# kfly_v3_0.net
KiCad netlist of a schematic drawn in EAGLE
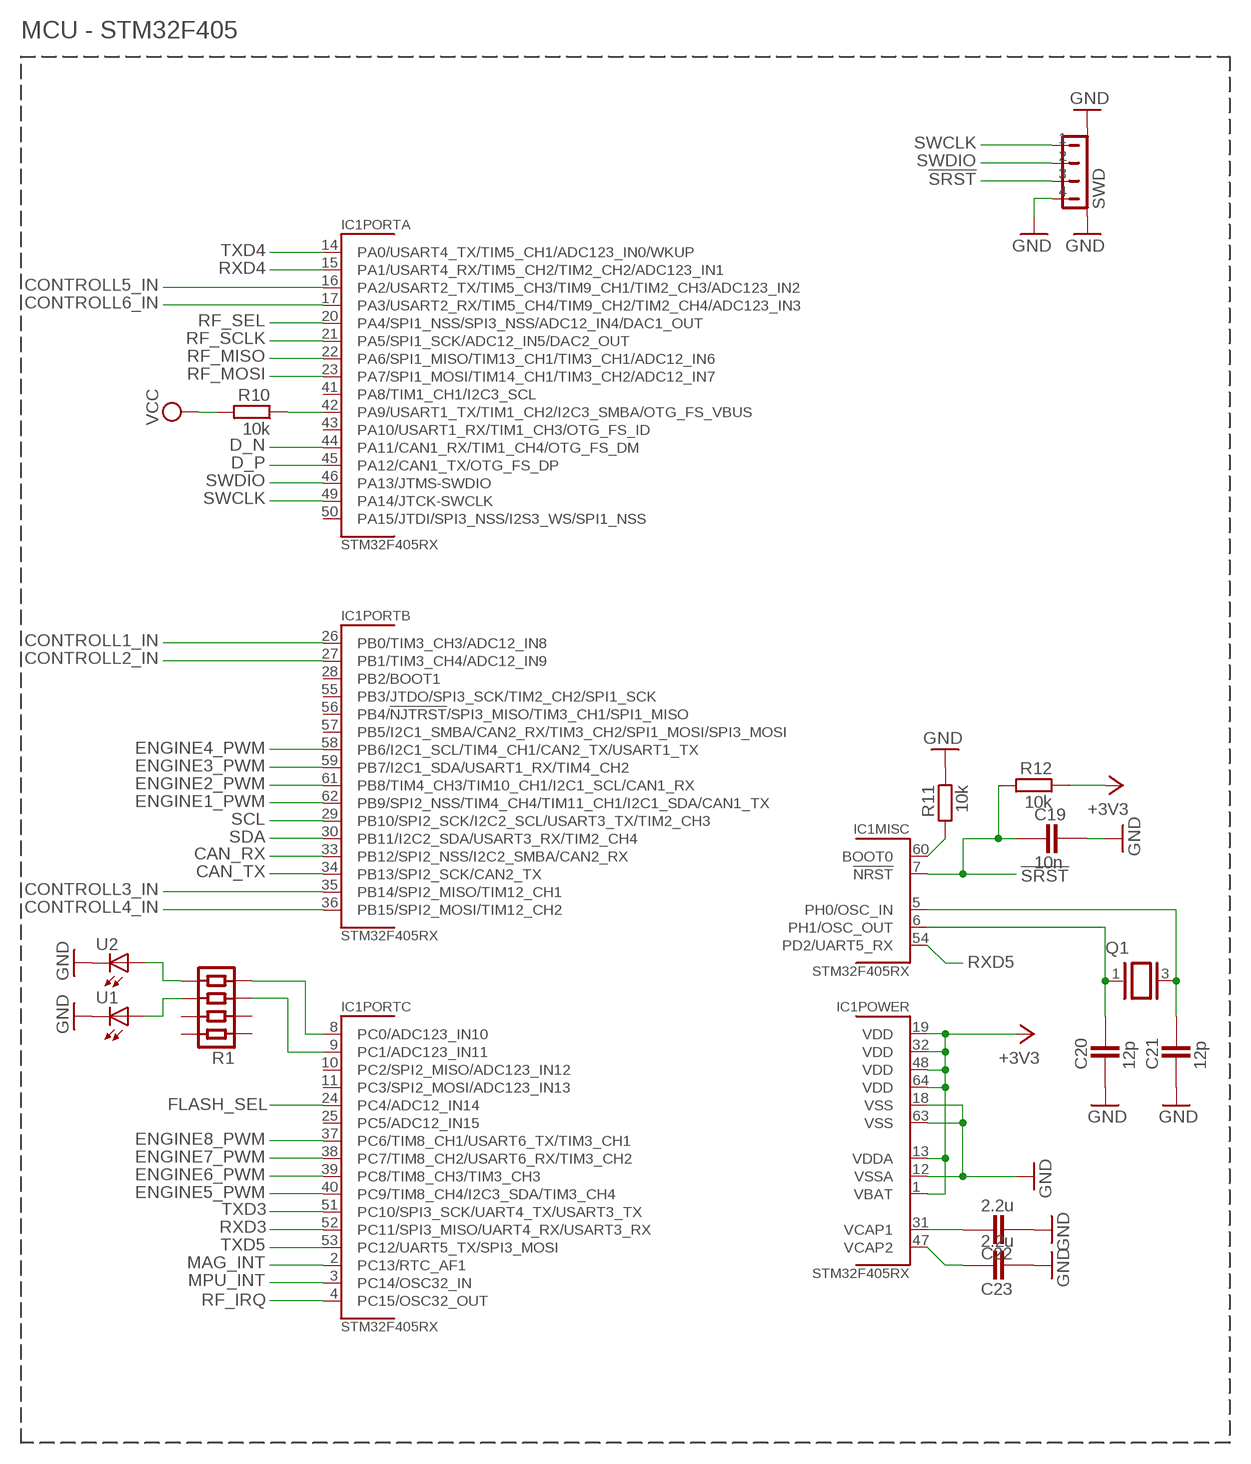
[diagram p0: schematic, sheet 1]
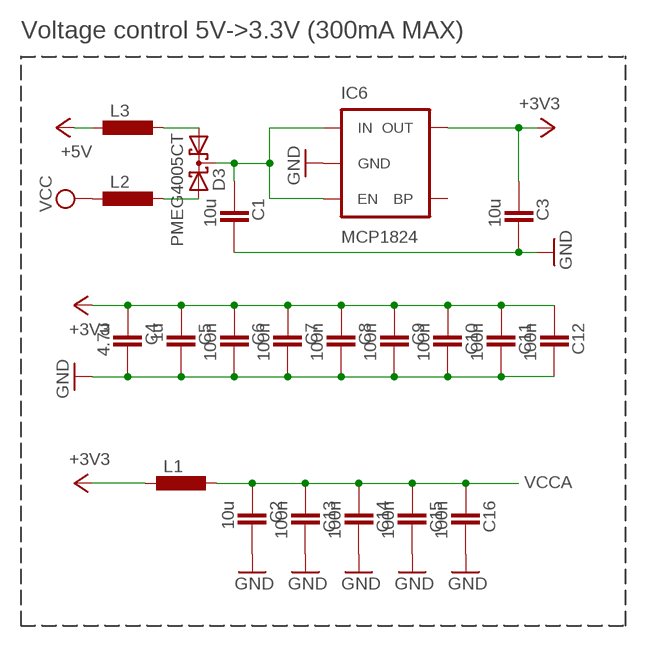
[diagram p1: schematic, sheet 2]
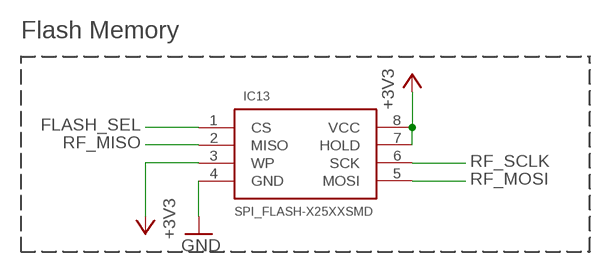
[diagram p2: schematic, sheet 3]
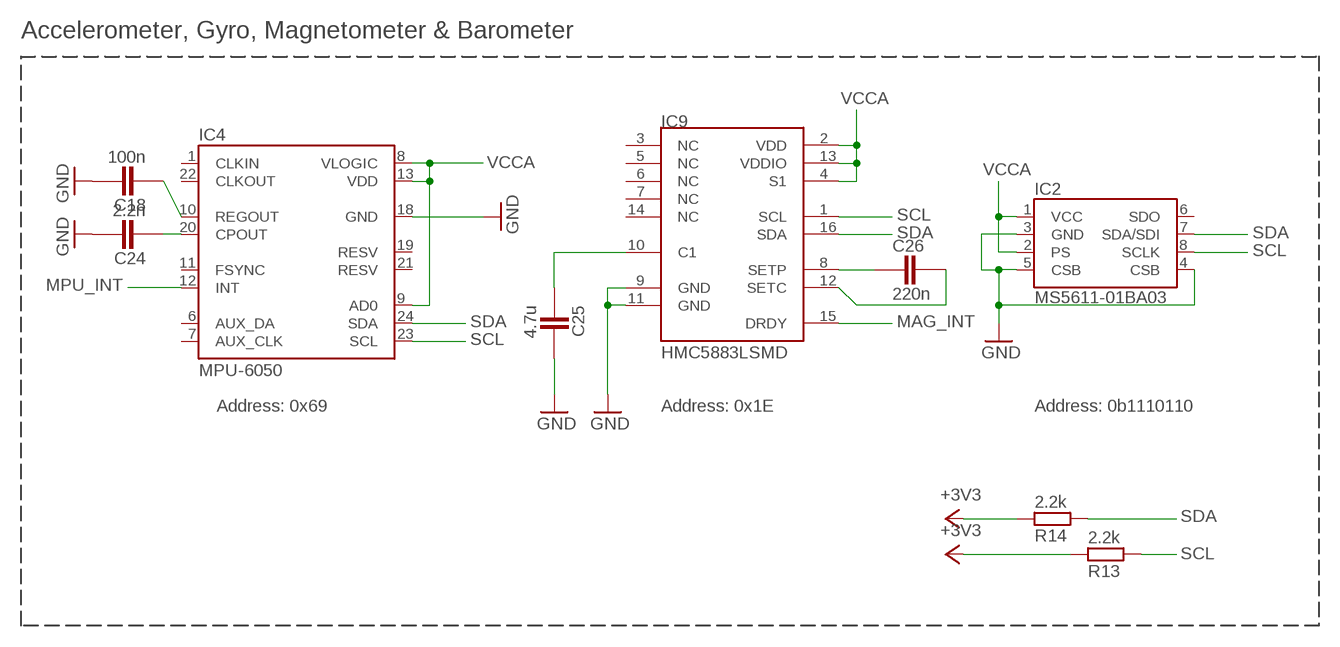
[diagram p3: schematic, sheet 4]
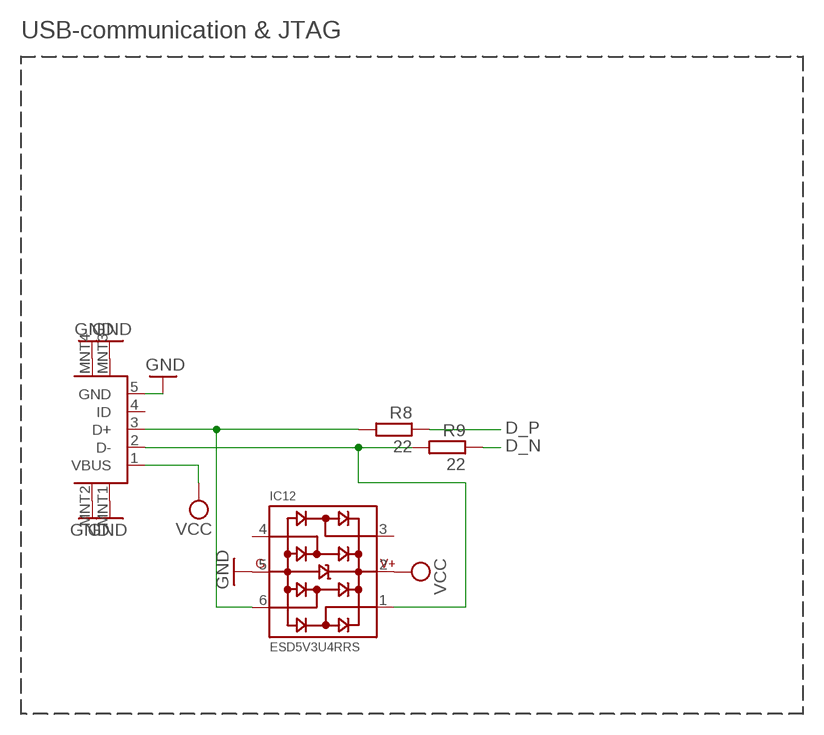
[diagram p4: schematic, sheet 5]
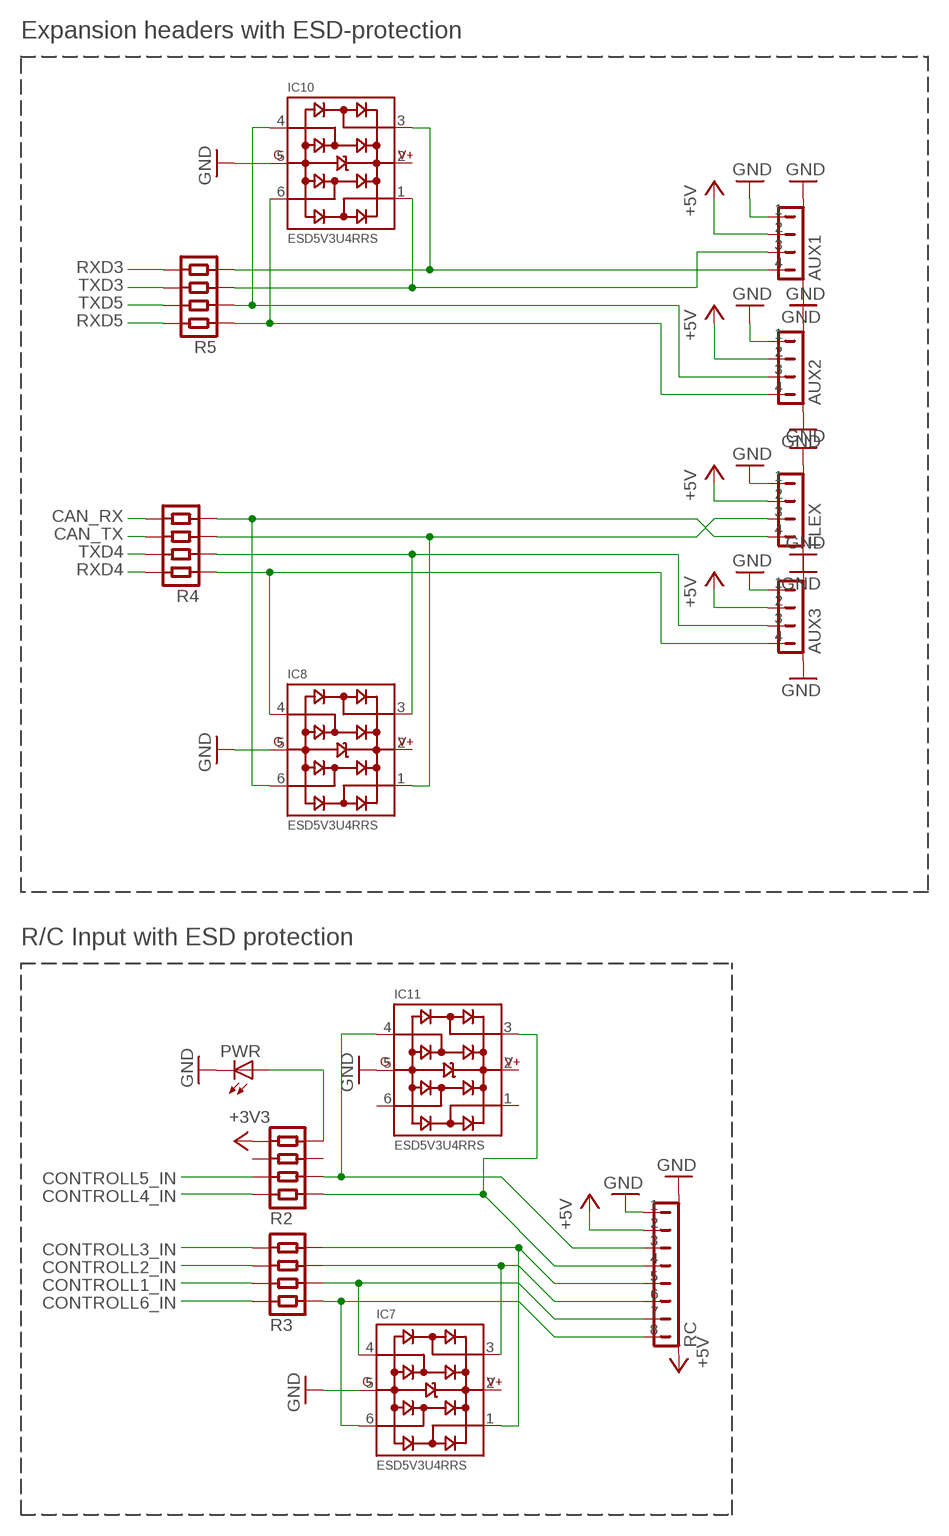
[diagram p5: schematic, sheet 6]
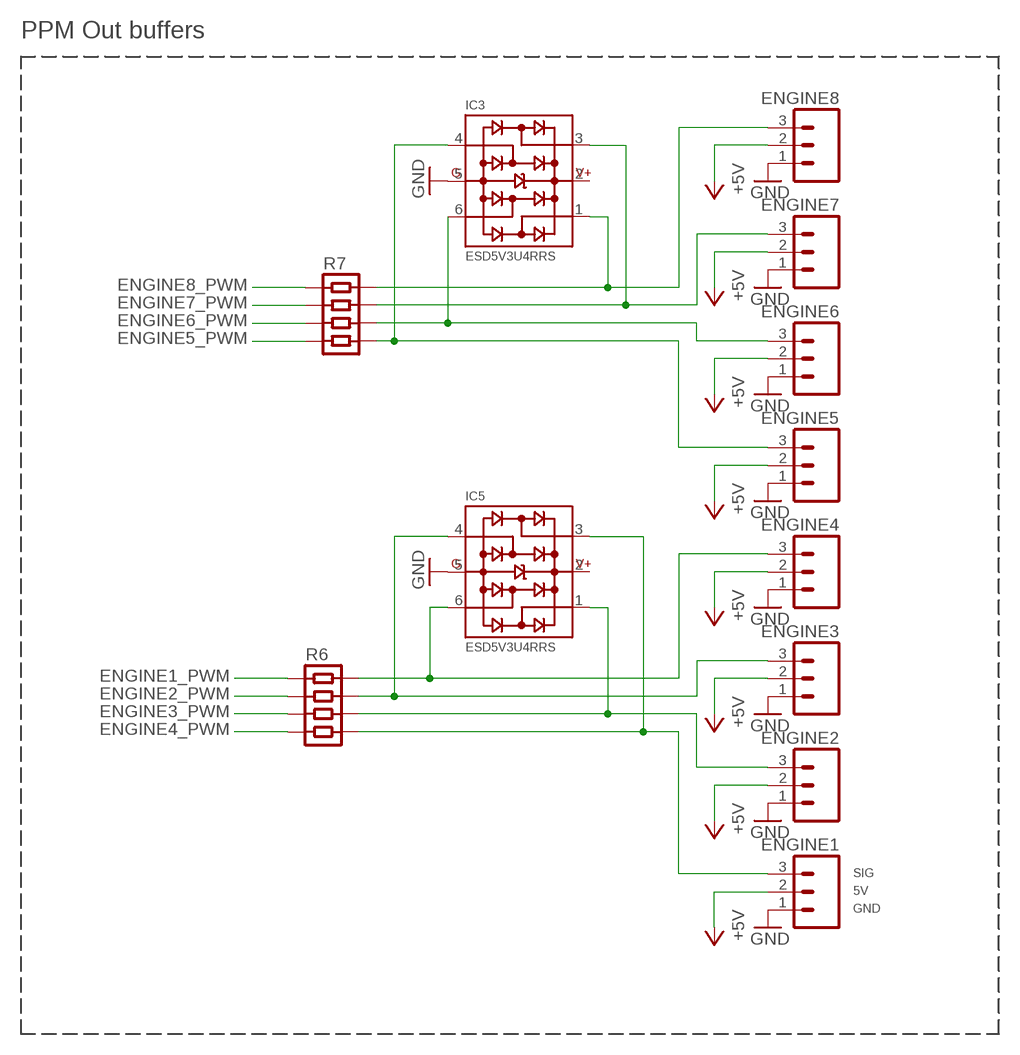
[diagram p6: schematic, sheet 7]
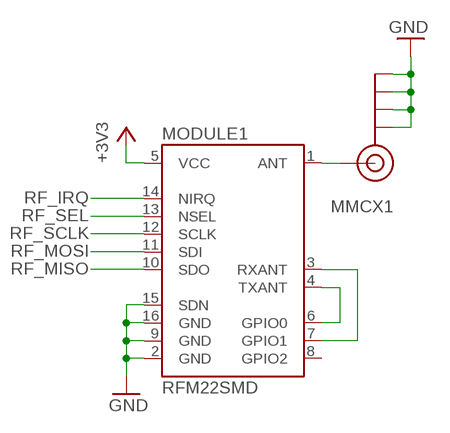
[diagram p7: schematic, sheet 8]

(export (version "E")
  (design (tool "Eeschema 10.0.6"))
  (components
    (comp (ref "C18")
      (value "100n")
      (footprint "eagle-import:CAPC1005X60N")
      (libsource (lib "eagle-import") (part "CAPACITOR_0402"))
    )
    (comp (ref "C24")
      (value "2.2n")
      (footprint "eagle-import:CAPC1005X60N")
      (libsource (lib "eagle-import") (part "CAPACITOR_0402"))
    )
    (comp (ref "C25")
      (value "4.7u")
      (footprint "eagle-import:CAPC1608X92N")
      (libsource (lib "eagle-import") (part "CAPACITOR_0603"))
    )
    (comp (ref "C26")
      (value "220n")
      (footprint "eagle-import:CAPC1608X92N")
      (libsource (lib "eagle-import") (part "CAPACITOR_0603"))
    )
    (comp (ref "IC2")
      (value "MS5611-01BA03")
      (footprint "eagle-import:MS5611")
      (libsource (lib "eagle-import") (part "MS5611-01BA01"))
    )
    (comp (ref "IC4")
      (value "MPU-6050")
      (footprint "eagle-import:QFN-24")
      (libsource (lib "eagle-import") (part "MPU-6050"))
    )
    (comp (ref "IC9")
      (value "HMC5883LSMD")
      (footprint "eagle-import:16LPCC")
      (libsource (lib "eagle-import") (part "HMC5883LSMD"))
    )
    (comp (ref "R13")
      (value "2.2k")
      (footprint "eagle-import:RESC1005X40AN")
      (libsource (lib "eagle-import") (part "RESISTOR_0402"))
    )
    (comp (ref "R14")
      (value "2.2k")
      (footprint "eagle-import:RESC1005X40AN")
      (libsource (lib "eagle-import") (part "RESISTOR_0402"))
    )
    (comp (ref "AUX1")
      (value "JST-4PIN-SIDE-1.0")
      (footprint "eagle-import:JST-4PIN-SIDE")
      (libsource (lib "eagle-import") (part "JST-4PIN-SIDE-1.0"))
    )
    (comp (ref "AUX2")
      (value "JST-4PIN-SIDE-1.0")
      (footprint "eagle-import:JST-4PIN-SIDE")
      (libsource (lib "eagle-import") (part "JST-4PIN-SIDE-1.0"))
    )
    (comp (ref "AUX3")
      (value "JST-4PIN-SIDE-1.0")
      (footprint "eagle-import:JST-4PIN-SIDE")
      (libsource (lib "eagle-import") (part "JST-4PIN-SIDE-1.0"))
    )
    (comp (ref "FLEX")
      (value "JST-4PIN-SIDE-1.0")
      (footprint "eagle-import:JST-4PIN-SIDE")
      (libsource (lib "eagle-import") (part "JST-4PIN-SIDE-1.0"))
    )
    (comp (ref "IC7")
      (value "ESD5V3U4RRS")
      (footprint "eagle-import:SOT363")
      (libsource (lib "eagle-import") (part "ESD5V3U4RRS"))
    )
    (comp (ref "IC8")
      (value "ESD5V3U4RRS")
      (footprint "eagle-import:SOT363")
      (libsource (lib "eagle-import") (part "ESD5V3U4RRS"))
    )
    (comp (ref "IC10")
      (value "ESD5V3U4RRS")
      (footprint "eagle-import:SOT363")
      (libsource (lib "eagle-import") (part "ESD5V3U4RRS"))
    )
    (comp (ref "IC11")
      (value "ESD5V3U4RRS")
      (footprint "eagle-import:SOT363")
      (libsource (lib "eagle-import") (part "ESD5V3U4RRS"))
    )
    (comp (ref "PWR")
      (value "LED0603")
      (footprint "eagle-import:LED-0603")
      (libsource (lib "eagle-import") (part "LED0603"))
    )
    (comp (ref "R2")
      (value "RESISTOR-4ARRAY-0804")
      (footprint "eagle-import:RESISTORARRAY_0804")
      (libsource (lib "eagle-import") (part "RESISTOR-4ARRAY-0804"))
    )
    (comp (ref "R3")
      (value "RESISTOR-4ARRAY-0804")
      (footprint "eagle-import:RESISTORARRAY_0804")
      (libsource (lib "eagle-import") (part "RESISTOR-4ARRAY-0804"))
    )
    (comp (ref "R4")
      (value "RESISTOR-4ARRAY-0804")
      (footprint "eagle-import:RESISTORARRAY_0804")
      (libsource (lib "eagle-import") (part "RESISTOR-4ARRAY-0804"))
    )
    (comp (ref "R5")
      (value "RESISTOR-4ARRAY-0804")
      (footprint "eagle-import:RESISTORARRAY_0804")
      (libsource (lib "eagle-import") (part "RESISTOR-4ARRAY-0804"))
    )
    (comp (ref "RC")
      (value "JST-8PIN-SIDE-1.0")
      (footprint "eagle-import:JST-8PIN-SIDE")
      (libsource (lib "eagle-import") (part "JST-8PIN-SIDE-1.0"))
    )
    (comp (ref "C19")
      (value "10n")
      (footprint "eagle-import:CAPC1005X60N")
      (libsource (lib "eagle-import") (part "CAPACITOR_0402"))
    )
    (comp (ref "C20")
      (value "12p")
      (footprint "eagle-import:CAPC1005X60N")
      (libsource (lib "eagle-import") (part "CAPACITOR_0402"))
    )
    (comp (ref "C21")
      (value "12p")
      (footprint "eagle-import:CAPC1005X60N")
      (libsource (lib "eagle-import") (part "CAPACITOR_0402"))
    )
    (comp (ref "C22")
      (value "2.2u")
      (footprint "eagle-import:CAPC1608X92N")
      (libsource (lib "eagle-import") (part "CAPACITOR_0603"))
    )
    (comp (ref "C23")
      (value "2.2u")
      (footprint "eagle-import:CAPC1608X92N")
      (libsource (lib "eagle-import") (part "CAPACITOR_0603"))
    )
    (comp (ref "IC1")
      (value "STM32F405RX")
      (footprint "eagle-import:LQFP64-10X10")
      (libsource (lib "eagle-import") (part "STM32F4X5RX"))
    )
    (comp (ref "Q1")
      (value "2.5X3.2CRYSTAL")
      (footprint "eagle-import:2.5X3.2CRYSTAL")
      (libsource (lib "eagle-import") (part "2.5X3.2CRYSTAL"))
    )
    (comp (ref "R1")
      (value "RESISTOR-4ARRAY-0804")
      (footprint "eagle-import:RESISTORARRAY_0804")
      (libsource (lib "eagle-import") (part "RESISTOR-4ARRAY-0804"))
    )
    (comp (ref "R10")
      (value "10k")
      (footprint "eagle-import:RESC1005X40AN")
      (libsource (lib "eagle-import") (part "RESISTOR_0402"))
    )
    (comp (ref "R11")
      (value "10k")
      (footprint "eagle-import:RESC1005X40AN")
      (libsource (lib "eagle-import") (part "RESISTOR_0402"))
    )
    (comp (ref "R12")
      (value "10k")
      (footprint "eagle-import:RESC1005X40AN")
      (libsource (lib "eagle-import") (part "RESISTOR_0402"))
    )
    (comp (ref "SWD")
      (value "JST-4PIN-SIDE-1.0")
      (footprint "eagle-import:JST-4PIN-SIDE")
      (libsource (lib "eagle-import") (part "JST-4PIN-SIDE-1.0"))
    )
    (comp (ref "U1")
      (value "LED0603")
      (footprint "eagle-import:LED-0603")
      (libsource (lib "eagle-import") (part "LED0603"))
    )
    (comp (ref "U2")
      (value "LED0603")
      (footprint "eagle-import:LED-0603")
      (libsource (lib "eagle-import") (part "LED0603"))
    )
    (comp (ref "IC13")
      (value "SPI_FLASH-X25XXSMD")
      (footprint "eagle-import:SO08")
      (libsource (lib "eagle-import") (part "SPI_FLASH-X25XXSMD"))
    )
    (comp (ref "C1")
      (value "10u")
      (footprint "eagle-import:CAPC1608X92N")
      (libsource (lib "eagle-import") (part "CAPACITOR_0603"))
    )
    (comp (ref "C2")
      (value "10u")
      (footprint "eagle-import:CAPC1608X92N")
      (libsource (lib "eagle-import") (part "CAPACITOR_0603"))
    )
    (comp (ref "C3")
      (value "10u")
      (footprint "eagle-import:CAPC1608X92N")
      (libsource (lib "eagle-import") (part "CAPACITOR_0603"))
    )
    (comp (ref "C4")
      (value "4.7u")
      (footprint "eagle-import:CAPC1608X92N")
      (libsource (lib "eagle-import") (part "CAPACITOR_0603"))
    )
    (comp (ref "C5")
      (value "1u")
      (footprint "eagle-import:CAPC1608X92N")
      (libsource (lib "eagle-import") (part "CAPACITOR_0603"))
    )
    (comp (ref "C6")
      (value "100n")
      (footprint "eagle-import:CAPC1005X60N")
      (libsource (lib "eagle-import") (part "CAPACITOR_0402"))
    )
    (comp (ref "C7")
      (value "100n")
      (footprint "eagle-import:CAPC1005X60N")
      (libsource (lib "eagle-import") (part "CAPACITOR_0402"))
    )
    (comp (ref "C8")
      (value "100n")
      (footprint "eagle-import:CAPC1005X60N")
      (libsource (lib "eagle-import") (part "CAPACITOR_0402"))
    )
    (comp (ref "C9")
      (value "100n")
      (footprint "eagle-import:CAPC1005X60N")
      (libsource (lib "eagle-import") (part "CAPACITOR_0402"))
    )
    (comp (ref "C10")
      (value "100n")
      (footprint "eagle-import:CAPC1005X60N")
      (libsource (lib "eagle-import") (part "CAPACITOR_0402"))
    )
    (comp (ref "C11")
      (value "100n")
      (footprint "eagle-import:CAPC1005X60N")
      (libsource (lib "eagle-import") (part "CAPACITOR_0402"))
    )
    (comp (ref "C12")
      (value "100n")
      (footprint "eagle-import:CAPC1005X60N")
      (libsource (lib "eagle-import") (part "CAPACITOR_0402"))
    )
    (comp (ref "C13")
      (value "100n")
      (footprint "eagle-import:CAPC1005X60N")
      (libsource (lib "eagle-import") (part "CAPACITOR_0402"))
    )
    (comp (ref "C14")
      (value "100n")
      (footprint "eagle-import:CAPC1005X60N")
      (libsource (lib "eagle-import") (part "CAPACITOR_0402"))
    )
    (comp (ref "C15")
      (value "100n")
      (footprint "eagle-import:CAPC1005X60N")
      (libsource (lib "eagle-import") (part "CAPACITOR_0402"))
    )
    (comp (ref "C16")
      (value "100n")
      (footprint "eagle-import:CAPC1005X60N")
      (libsource (lib "eagle-import") (part "CAPACITOR_0402"))
    )
    (comp (ref "D3")
      (value "PMEG4005CT")
      (footprint "eagle-import:SOT23")
      (libsource (lib "eagle-import") (part "BAS40-05"))
    )
    (comp (ref "IC6")
      (value "MCP1824")
      (footprint "eagle-import:SOT23-5")
      (libsource (lib "eagle-import") (part "V_REG_LDOSMD"))
    )
    (comp (ref "L1")
      (value "INDUCTOR_0603")
      (footprint "eagle-import:INDC1608X95N")
      (libsource (lib "eagle-import") (part "INDUCTOR_0603"))
    )
    (comp (ref "L2")
      (value "INDUCTOR_0603")
      (footprint "eagle-import:INDC1608X95N")
      (libsource (lib "eagle-import") (part "INDUCTOR_0603"))
    )
    (comp (ref "L3")
      (value "INDUCTOR_0603")
      (footprint "eagle-import:INDC1608X95N")
      (libsource (lib "eagle-import") (part "INDUCTOR_0603"))
    )
    (comp (ref "MMCX1")
      (value "MMCX")
      (footprint "eagle-import:MMCX_THROUGHHOLE_RIGHTANGLE")
      (libsource (lib "eagle-import") (part "MMCX"))
    )
    (comp (ref "MODULE1")
      (value "RFM22SMD")
      (footprint "eagle-import:RFM22-XXX-S2")
      (libsource (lib "eagle-import") (part "RFM22SMD"))
    )
    (comp (ref "IC12")
      (value "ESD5V3U4RRS")
      (footprint "eagle-import:SOT363")
      (libsource (lib "eagle-import") (part "ESD5V3U4RRS"))
    )
    (comp (ref "R8")
      (value "22")
      (footprint "eagle-import:RESC1005X40AN")
      (libsource (lib "eagle-import") (part "RESISTOR_0402"))
    )
    (comp (ref "R9")
      (value "22")
      (footprint "eagle-import:RESC1005X40AN")
      (libsource (lib "eagle-import") (part "RESISTOR_0402"))
    )
    (comp (ref "USB1")
      (value "USB-MICRO-B-BOTTOM")
      (footprint "eagle-import:MICROUSB_TYPEB_SURFACE")
      (libsource (lib "eagle-import") (part "USB-MICRO-B-BOTTOM"))
    )
    (comp (ref "ENGINE1")
      (value "M03")
      (footprint "eagle-import:M03")
      (libsource (lib "eagle-import") (part "M03"))
    )
    (comp (ref "ENGINE2")
      (value "M03")
      (footprint "eagle-import:M03")
      (libsource (lib "eagle-import") (part "M03"))
    )
    (comp (ref "ENGINE3")
      (value "M03")
      (footprint "eagle-import:M03")
      (libsource (lib "eagle-import") (part "M03"))
    )
    (comp (ref "ENGINE4")
      (value "M03")
      (footprint "eagle-import:M03")
      (libsource (lib "eagle-import") (part "M03"))
    )
    (comp (ref "ENGINE5")
      (value "M03")
      (footprint "eagle-import:M03")
      (libsource (lib "eagle-import") (part "M03"))
    )
    (comp (ref "ENGINE6")
      (value "M03")
      (footprint "eagle-import:M03")
      (libsource (lib "eagle-import") (part "M03"))
    )
    (comp (ref "ENGINE7")
      (value "M03")
      (footprint "eagle-import:M03")
      (libsource (lib "eagle-import") (part "M03"))
    )
    (comp (ref "ENGINE8")
      (value "M03")
      (footprint "eagle-import:M03")
      (libsource (lib "eagle-import") (part "M03"))
    )
    (comp (ref "IC3")
      (value "ESD5V3U4RRS")
      (footprint "eagle-import:SOT363")
      (libsource (lib "eagle-import") (part "ESD5V3U4RRS"))
    )
    (comp (ref "IC5")
      (value "ESD5V3U4RRS")
      (footprint "eagle-import:SOT363")
      (libsource (lib "eagle-import") (part "ESD5V3U4RRS"))
    )
    (comp (ref "R6")
      (value "RESISTOR-4ARRAY-0804")
      (footprint "eagle-import:RESISTORARRAY_0804")
      (libsource (lib "eagle-import") (part "RESISTOR-4ARRAY-0804"))
    )
    (comp (ref "R7")
      (value "RESISTOR-4ARRAY-0804")
      (footprint "eagle-import:RESISTORARRAY_0804")
      (libsource (lib "eagle-import") (part "RESISTOR-4ARRAY-0804"))
    )
  )
  (nets
    (net (code "1") (name "+3V3") (class "Default")
      (node (ref "C10") (pin "1") (pinfunction "1_1") (pintype "passive"))
      (node (ref "C11") (pin "1") (pinfunction "1_1") (pintype "passive"))
      (node (ref "C12") (pin "1") (pinfunction "1_1") (pintype "passive"))
      (node (ref "C3") (pin "1") (pinfunction "1_1") (pintype "passive"))
      (node (ref "C4") (pin "1") (pinfunction "1_1") (pintype "passive"))
      (node (ref "C5") (pin "1") (pinfunction "1_1") (pintype "passive"))
      (node (ref "C6") (pin "1") (pinfunction "1_1") (pintype "passive"))
      (node (ref "C7") (pin "1") (pinfunction "1_1") (pintype "passive"))
      (node (ref "C8") (pin "1") (pinfunction "1_1") (pintype "passive"))
      (node (ref "C9") (pin "1") (pinfunction "1_1") (pintype "passive"))
      (node (ref "IC1") (pin "1") (pinfunction "VBAT_1") (pintype "bidirectional"))
      (node (ref "IC1") (pin "13") (pinfunction "VDDA_13") (pintype "bidirectional"))
      (node (ref "IC1") (pin "19") (pinfunction "VDD_19") (pintype "bidirectional"))
      (node (ref "IC1") (pin "32") (pinfunction "VDD_32") (pintype "bidirectional"))
      (node (ref "IC1") (pin "48") (pinfunction "VDD_48") (pintype "bidirectional"))
      (node (ref "IC1") (pin "64") (pinfunction "VDD_64") (pintype "bidirectional"))
      (node (ref "IC13") (pin "3") (pinfunction "WP_3") (pintype "bidirectional"))
      (node (ref "IC13") (pin "7") (pinfunction "HOLD_7") (pintype "bidirectional"))
      (node (ref "IC13") (pin "8") (pinfunction "VCC_8") (pintype "bidirectional"))
      (node (ref "IC6") (pin "5") (pinfunction "OUT_5") (pintype "passive"))
      (node (ref "L1") (pin "1") (pinfunction "1_1") (pintype "passive"))
      (node (ref "MODULE1") (pin "5") (pinfunction "VCC_5") (pintype "bidirectional"))
      (node (ref "R12") (pin "1") (pinfunction "1_1") (pintype "passive"))
      (node (ref "R13") (pin "1") (pinfunction "1_1") (pintype "passive"))
      (node (ref "R14") (pin "1") (pinfunction "1_1") (pintype "passive"))
      (node (ref "R2") (pin "4") (pinfunction "4_4") (pintype "bidirectional"))
    )
    (net (code "2") (name "+5V") (class "Default")
      (node (ref "AUX1") (pin "2") (pinfunction "2_2") (pintype "bidirectional"))
      (node (ref "AUX2") (pin "2") (pinfunction "2_2") (pintype "bidirectional"))
      (node (ref "AUX3") (pin "2") (pinfunction "2_2") (pintype "bidirectional"))
      (node (ref "ENGINE1") (pin "2") (pinfunction "2_2") (pintype "passive"))
      (node (ref "ENGINE2") (pin "2") (pinfunction "2_2") (pintype "passive"))
      (node (ref "ENGINE3") (pin "2") (pinfunction "2_2") (pintype "passive"))
      (node (ref "ENGINE4") (pin "2") (pinfunction "2_2") (pintype "passive"))
      (node (ref "ENGINE5") (pin "2") (pinfunction "2_2") (pintype "passive"))
      (node (ref "ENGINE6") (pin "2") (pinfunction "2_2") (pintype "passive"))
      (node (ref "ENGINE7") (pin "2") (pinfunction "2_2") (pintype "passive"))
      (node (ref "ENGINE8") (pin "2") (pinfunction "2_2") (pintype "passive"))
      (node (ref "FLEX") (pin "2") (pinfunction "2_2") (pintype "bidirectional"))
      (node (ref "L3") (pin "1") (pinfunction "1_1") (pintype "passive"))
      (node (ref "RC") (pin "2") (pinfunction "2_2") (pintype "bidirectional"))
      (node (ref "RC") (pin "NC2") (pinfunction "GND2_NC2") (pintype "bidirectional"))
    )
    (net (code "3") (name "CAN_RX") (class "Default")
      (node (ref "IC1") (pin "33") (pinfunction "PB12/SPI2_NSS/I2C2_SMBA/CAN2_RX_33") (pintype "bidirectional"))
      (node (ref "R4") (pin "5") (pinfunction "5_5") (pintype "bidirectional"))
    )
    (net (code "4") (name "CAN_TX") (class "Default")
      (node (ref "IC1") (pin "34") (pinfunction "PB13/SPI2_SCK/CAN2_TX_34") (pintype "bidirectional"))
      (node (ref "R4") (pin "6") (pinfunction "6_6") (pintype "bidirectional"))
    )
    (net (code "5") (name "CONTROLL1_IN") (class "Default")
      (node (ref "IC1") (pin "26") (pinfunction "PB0/TIM3_CH3/ADC12_IN8_26") (pintype "bidirectional"))
      (node (ref "R3") (pin "2") (pinfunction "2_2") (pintype "bidirectional"))
    )
    (net (code "6") (name "CONTROLL2_IN") (class "Default")
      (node (ref "IC1") (pin "27") (pinfunction "PB1/TIM3_CH4/ADC12_IN9_27") (pintype "bidirectional"))
      (node (ref "R3") (pin "3") (pinfunction "3_3") (pintype "bidirectional"))
    )
    (net (code "7") (name "CONTROLL3_IN") (class "Default")
      (node (ref "IC1") (pin "35") (pinfunction "PB14/SPI2_MISO/TIM12_CH1_35") (pintype "bidirectional"))
      (node (ref "R3") (pin "4") (pinfunction "4_4") (pintype "bidirectional"))
    )
    (net (code "8") (name "CONTROLL4_IN") (class "Default")
      (node (ref "IC1") (pin "36") (pinfunction "PB15/SPI2_MOSI/TIM12_CH2_36") (pintype "bidirectional"))
      (node (ref "R2") (pin "1") (pinfunction "1_1") (pintype "bidirectional"))
    )
    (net (code "9") (name "CONTROLL5_IN") (class "Default")
      (node (ref "IC1") (pin "16") (pinfunction "PA2/USART2_TX/TIM5_CH3/TIM9_CH1/TIM2_CH3/ADC123_IN2_16") (pintype "bidirectional"))
      (node (ref "R2") (pin "2") (pinfunction "2_2") (pintype "bidirectional"))
    )
    (net (code "10") (name "CONTROLL6_IN") (class "Default")
      (node (ref "IC1") (pin "17") (pinfunction "PA3/USART2_RX/TIM5_CH4/TIM9_CH2/TIM2_CH4/ADC123_IN3_17") (pintype "bidirectional"))
      (node (ref "R3") (pin "1") (pinfunction "1_1") (pintype "bidirectional"))
    )
    (net (code "11") (name "D_N") (class "Default")
      (node (ref "IC1") (pin "44") (pinfunction "PA11/CAN1_RX/TIM1_CH4/OTG_FS_DM_44") (pintype "bidirectional"))
      (node (ref "R9") (pin "1") (pinfunction "1_1") (pintype "passive"))
    )
    (net (code "12") (name "D_P") (class "Default")
      (node (ref "IC1") (pin "45") (pinfunction "PA12/CAN1_TX/OTG_FS_DP_45") (pintype "bidirectional"))
      (node (ref "R8") (pin "1") (pinfunction "1_1") (pintype "passive"))
    )
    (net (code "13") (name "ENGINE1_PWM") (class "Default")
      (node (ref "IC1") (pin "62") (pinfunction "PB9/SPI2_NSS/TIM4_CH4/TIM11_CH1/I2C1_SDA/CAN1_TX_62") (pintype "bidirectional"))
      (node (ref "R6") (pin "1") (pinfunction "1_1") (pintype "bidirectional"))
    )
    (net (code "14") (name "ENGINE2_PWM") (class "Default")
      (node (ref "IC1") (pin "61") (pinfunction "PB8/TIM4_CH3/TIM10_CH1/I2C1_SCL/CAN1_RX_61") (pintype "bidirectional"))
      (node (ref "R6") (pin "2") (pinfunction "2_2") (pintype "bidirectional"))
    )
    (net (code "15") (name "ENGINE3_PWM") (class "Default")
      (node (ref "IC1") (pin "59") (pinfunction "PB7/I2C1_SDA/USART1_RX/TIM4_CH2_59") (pintype "bidirectional"))
      (node (ref "R6") (pin "3") (pinfunction "3_3") (pintype "bidirectional"))
    )
    (net (code "16") (name "ENGINE4_PWM") (class "Default")
      (node (ref "IC1") (pin "58") (pinfunction "PB6/I2C1_SCL/TIM4_CH1/CAN2_TX/USART1_TX_58") (pintype "bidirectional"))
      (node (ref "R6") (pin "4") (pinfunction "4_4") (pintype "bidirectional"))
    )
    (net (code "17") (name "ENGINE5_PWM") (class "Default")
      (node (ref "IC1") (pin "40") (pinfunction "PC9/TIM8_CH4/I2C3_SDA/TIM3_CH4_40") (pintype "bidirectional"))
      (node (ref "R7") (pin "4") (pinfunction "4_4") (pintype "bidirectional"))
    )
    (net (code "18") (name "ENGINE6_PWM") (class "Default")
      (node (ref "IC1") (pin "39") (pinfunction "PC8/TIM8_CH3/TIM3_CH3_39") (pintype "bidirectional"))
      (node (ref "R7") (pin "3") (pinfunction "3_3") (pintype "bidirectional"))
    )
    (net (code "19") (name "ENGINE7_PWM") (class "Default")
      (node (ref "IC1") (pin "38") (pinfunction "PC7/TIM8_CH2/USART6_RX/TIM3_CH2_38") (pintype "bidirectional"))
      (node (ref "R7") (pin "2") (pinfunction "2_2") (pintype "bidirectional"))
    )
    (net (code "20") (name "ENGINE8_PWM") (class "Default")
      (node (ref "IC1") (pin "37") (pinfunction "PC6/TIM8_CH1/USART6_TX/TIM3_CH1_37") (pintype "bidirectional"))
      (node (ref "R7") (pin "1") (pinfunction "1_1") (pintype "bidirectional"))
    )
    (net (code "21") (name "FLASH_SEL") (class "Default")
      (node (ref "IC1") (pin "24") (pinfunction "PC4/ADC12_IN14_24") (pintype "bidirectional"))
      (node (ref "IC13") (pin "1") (pinfunction "CS_1") (pintype "bidirectional"))
    )
    (net (code "22") (name "GND") (class "Default")
      (node (ref "AUX1") (pin "1") (pinfunction "1_1") (pintype "bidirectional"))
      (node (ref "AUX1") (pin "NC1") (pinfunction "P1_NC1") (pintype "bidirectional"))
      (node (ref "AUX1") (pin "NC2") (pinfunction "P2_NC2") (pintype "bidirectional"))
      (node (ref "AUX2") (pin "1") (pinfunction "1_1") (pintype "bidirectional"))
      (node (ref "AUX2") (pin "NC1") (pinfunction "P1_NC1") (pintype "bidirectional"))
      (node (ref "AUX2") (pin "NC2") (pinfunction "P2_NC2") (pintype "bidirectional"))
      (node (ref "AUX3") (pin "1") (pinfunction "1_1") (pintype "bidirectional"))
      (node (ref "AUX3") (pin "NC1") (pinfunction "P1_NC1") (pintype "bidirectional"))
      (node (ref "AUX3") (pin "NC2") (pinfunction "P2_NC2") (pintype "bidirectional"))
      (node (ref "C1") (pin "2") (pinfunction "2_2") (pintype "passive"))
      (node (ref "C10") (pin "2") (pinfunction "2_2") (pintype "passive"))
      (node (ref "C11") (pin "2") (pinfunction "2_2") (pintype "passive"))
      (node (ref "C12") (pin "2") (pinfunction "2_2") (pintype "passive"))
      (node (ref "C13") (pin "2") (pinfunction "2_2") (pintype "passive"))
      (node (ref "C14") (pin "2") (pinfunction "2_2") (pintype "passive"))
      (node (ref "C15") (pin "2") (pinfunction "2_2") (pintype "passive"))
      (node (ref "C16") (pin "2") (pinfunction "2_2") (pintype "passive"))
      (node (ref "C18") (pin "2") (pinfunction "2_2") (pintype "passive"))
      (node (ref "C19") (pin "2") (pinfunction "2_2") (pintype "passive"))
      (node (ref "C2") (pin "2") (pinfunction "2_2") (pintype "passive"))
      (node (ref "C20") (pin "1") (pinfunction "1_1") (pintype "passive"))
      (node (ref "C21") (pin "1") (pinfunction "1_1") (pintype "passive"))
      (node (ref "C22") (pin "2") (pinfunction "2_2") (pintype "passive"))
      (node (ref "C23") (pin "2") (pinfunction "2_2") (pintype "passive"))
      (node (ref "C24") (pin "2") (pinfunction "2_2") (pintype "passive"))
      (node (ref "C25") (pin "2") (pinfunction "2_2") (pintype "passive"))
      (node (ref "C3") (pin "2") (pinfunction "2_2") (pintype "passive"))
      (node (ref "C4") (pin "2") (pinfunction "2_2") (pintype "passive"))
      (node (ref "C5") (pin "2") (pinfunction "2_2") (pintype "passive"))
      (node (ref "C6") (pin "2") (pinfunction "2_2") (pintype "passive"))
      (node (ref "C7") (pin "2") (pinfunction "2_2") (pintype "passive"))
      (node (ref "C8") (pin "2") (pinfunction "2_2") (pintype "passive"))
      (node (ref "C9") (pin "2") (pinfunction "2_2") (pintype "passive"))
      (node (ref "ENGINE1") (pin "1") (pinfunction "1_1") (pintype "passive"))
      (node (ref "ENGINE2") (pin "1") (pinfunction "1_1") (pintype "passive"))
      (node (ref "ENGINE3") (pin "1") (pinfunction "1_1") (pintype "passive"))
      (node (ref "ENGINE4") (pin "1") (pinfunction "1_1") (pintype "passive"))
      (node (ref "ENGINE5") (pin "1") (pinfunction "1_1") (pintype "passive"))
      (node (ref "ENGINE6") (pin "1") (pinfunction "1_1") (pintype "passive"))
      (node (ref "ENGINE7") (pin "1") (pinfunction "1_1") (pintype "passive"))
      (node (ref "ENGINE8") (pin "1") (pinfunction "1_1") (pintype "passive"))
      (node (ref "FLEX") (pin "1") (pinfunction "1_1") (pintype "bidirectional"))
      (node (ref "FLEX") (pin "NC1") (pinfunction "P1_NC1") (pintype "bidirectional"))
      (node (ref "FLEX") (pin "NC2") (pinfunction "P2_NC2") (pintype "bidirectional"))
      (node (ref "IC1") (pin "12") (pinfunction "VSSA_12") (pintype "bidirectional"))
      (node (ref "IC1") (pin "18") (pinfunction "VSS_18") (pintype "bidirectional"))
      (node (ref "IC1") (pin "63") (pinfunction "VSS_63") (pintype "bidirectional"))
      (node (ref "IC10") (pin "5") (pinfunction "5_5") (pintype "bidirectional"))
      (node (ref "IC11") (pin "5") (pinfunction "5_5") (pintype "bidirectional"))
      (node (ref "IC12") (pin "5") (pinfunction "5_5") (pintype "bidirectional"))
      (node (ref "IC13") (pin "4") (pinfunction "GND_4") (pintype "bidirectional"))
      (node (ref "IC2") (pin "3") (pinfunction "GND_3") (pintype "bidirectional"))
      (node (ref "IC2") (pin "4") (pinfunction "CSB_4") (pintype "bidirectional"))
      (node (ref "IC2") (pin "5") (pinfunction "CSB_5") (pintype "bidirectional"))
      (node (ref "IC3") (pin "5") (pinfunction "5_5") (pintype "bidirectional"))
      (node (ref "IC4") (pin "18") (pinfunction "GND_18") (pintype "bidirectional"))
      (node (ref "IC5") (pin "5") (pinfunction "5_5") (pintype "bidirectional"))
      (node (ref "IC6") (pin "2") (pinfunction "GND_2") (pintype "input"))
      (node (ref "IC7") (pin "5") (pinfunction "5_5") (pintype "bidirectional"))
      (node (ref "IC8") (pin "5") (pinfunction "5_5") (pintype "bidirectional"))
      (node (ref "IC9") (pin "11") (pinfunction "GND_11") (pintype "bidirectional"))
      (node (ref "IC9") (pin "9") (pinfunction "GND_9") (pintype "bidirectional"))
      (node (ref "MMCX1") (pin "G1") (pinfunction "GND_G1") (pintype "bidirectional"))
      (node (ref "MMCX1") (pin "G2") (pinfunction "GND_G2") (pintype "bidirectional"))
      (node (ref "MMCX1") (pin "G3") (pinfunction "GND_G3") (pintype "bidirectional"))
      (node (ref "MMCX1") (pin "G4") (pinfunction "GND_G4") (pintype "bidirectional"))
      (node (ref "MODULE1") (pin "15") (pinfunction "SDN_15") (pintype "input"))
      (node (ref "MODULE1") (pin "16") (pinfunction "GND_16") (pintype "power_in"))
      (node (ref "MODULE1") (pin "2") (pinfunction "GND_2") (pintype "power_in"))
      (node (ref "MODULE1") (pin "9") (pinfunction "GND_9") (pintype "power_in"))
      (node (ref "PWR") (pin "C") (pinfunction "C_C") (pintype "passive"))
      (node (ref "R11") (pin "1") (pinfunction "1_1") (pintype "passive"))
      (node (ref "RC") (pin "1") (pinfunction "1_1") (pintype "bidirectional"))
      (node (ref "RC") (pin "NC1") (pinfunction "GND1_NC1") (pintype "bidirectional"))
      (node (ref "SWD") (pin "4") (pinfunction "4_4") (pintype "bidirectional"))
      (node (ref "SWD") (pin "NC1") (pinfunction "P1_NC1") (pintype "bidirectional"))
      (node (ref "SWD") (pin "NC2") (pinfunction "P2_NC2") (pintype "bidirectional"))
      (node (ref "U1") (pin "C") (pinfunction "C_C") (pintype "passive"))
      (node (ref "U2") (pin "C") (pinfunction "C_C") (pintype "passive"))
      (node (ref "USB1") (pin "5") (pinfunction "GND_5") (pintype "bidirectional"))
      (node (ref "USB1") (pin "MNT1") (pinfunction "MTN1_MNT1") (pintype "bidirectional"))
      (node (ref "USB1") (pin "MNT2") (pinfunction "MTN2_MNT2") (pintype "bidirectional"))
      (node (ref "USB1") (pin "MNT3") (pinfunction "MTN3_MNT3") (pintype "bidirectional"))
      (node (ref "USB1") (pin "MNT4") (pinfunction "MTN4_MNT4") (pintype "bidirectional"))
    )
    (net (code "23") (name "MAG_INT") (class "Default")
      (node (ref "IC1") (pin "2") (pinfunction "PC13/RTC_AF1_2") (pintype "bidirectional"))
      (node (ref "IC9") (pin "15") (pinfunction "DRDY_15") (pintype "bidirectional"))
    )
    (net (code "24") (name "MPU_INT") (class "Default")
      (node (ref "IC1") (pin "3") (pinfunction "PC14/OSC32_IN_3") (pintype "bidirectional"))
      (node (ref "IC4") (pin "12") (pinfunction "INT_12") (pintype "bidirectional"))
    )
    (net (code "25") (name "Net-(AUX1-Pad3)") (class "Default")
      (node (ref "AUX1") (pin "3") (pinfunction "3_3") (pintype "bidirectional"))
      (node (ref "IC10") (pin "1") (pinfunction "1_1") (pintype "bidirectional"))
      (node (ref "R5") (pin "3") (pinfunction "3_3") (pintype "bidirectional"))
    )
    (net (code "26") (name "Net-(AUX1-Pad4)") (class "Default")
      (node (ref "AUX1") (pin "4") (pinfunction "4_4") (pintype "bidirectional"))
      (node (ref "IC10") (pin "3") (pinfunction "3_3") (pintype "bidirectional"))
      (node (ref "R5") (pin "4") (pinfunction "4_4") (pintype "bidirectional"))
    )
    (net (code "27") (name "Net-(AUX2-Pad3)") (class "Default")
      (node (ref "AUX2") (pin "3") (pinfunction "3_3") (pintype "bidirectional"))
      (node (ref "IC10") (pin "4") (pinfunction "4_4") (pintype "bidirectional"))
      (node (ref "R5") (pin "2") (pinfunction "2_2") (pintype "bidirectional"))
    )
    (net (code "28") (name "Net-(AUX2-Pad4)") (class "Default")
      (node (ref "AUX2") (pin "4") (pinfunction "4_4") (pintype "bidirectional"))
      (node (ref "IC10") (pin "6") (pinfunction "6_6") (pintype "bidirectional"))
      (node (ref "R5") (pin "1") (pinfunction "1_1") (pintype "bidirectional"))
    )
    (net (code "29") (name "Net-(AUX3-Pad3)") (class "Default")
      (node (ref "AUX3") (pin "3") (pinfunction "3_3") (pintype "bidirectional"))
      (node (ref "IC8") (pin "3") (pinfunction "3_3") (pintype "bidirectional"))
      (node (ref "R4") (pin "2") (pinfunction "2_2") (pintype "bidirectional"))
    )
    (net (code "30") (name "Net-(AUX3-Pad4)") (class "Default")
      (node (ref "AUX3") (pin "4") (pinfunction "4_4") (pintype "bidirectional"))
      (node (ref "IC8") (pin "4") (pinfunction "4_4") (pintype "bidirectional"))
      (node (ref "R4") (pin "1") (pinfunction "1_1") (pintype "bidirectional"))
    )
    (net (code "31") (name "Net-(D3-A1)") (class "Default")
      (node (ref "D3") (pin "1") (pinfunction "A1_1") (pintype "passive"))
      (node (ref "L3") (pin "2") (pinfunction "2_2") (pintype "passive"))
    )
    (net (code "32") (name "Net-(D3-A2)") (class "Default")
      (node (ref "D3") (pin "2") (pinfunction "A2_2") (pintype "passive"))
      (node (ref "L2") (pin "2") (pinfunction "2_2") (pintype "passive"))
    )
    (net (code "33") (name "Net-(D3-C)") (class "Default")
      (node (ref "C1") (pin "1") (pinfunction "1_1") (pintype "passive"))
      (node (ref "D3") (pin "3") (pinfunction "C_3") (pintype "passive"))
      (node (ref "IC6") (pin "1") (pinfunction "IN_1") (pintype "input"))
      (node (ref "IC6") (pin "3") (pinfunction "EN_3") (pintype "input"))
    )
    (net (code "34") (name "Net-(ENGINE1-Pad3)") (class "Default")
      (node (ref "ENGINE1") (pin "3") (pinfunction "3_3") (pintype "passive"))
      (node (ref "IC5") (pin "3") (pinfunction "3_3") (pintype "bidirectional"))
      (node (ref "R6") (pin "5") (pinfunction "5_5") (pintype "bidirectional"))
    )
    (net (code "35") (name "Net-(ENGINE2-Pad3)") (class "Default")
      (node (ref "ENGINE2") (pin "3") (pinfunction "3_3") (pintype "passive"))
      (node (ref "IC5") (pin "1") (pinfunction "1_1") (pintype "bidirectional"))
      (node (ref "R6") (pin "6") (pinfunction "6_6") (pintype "bidirectional"))
    )
    (net (code "36") (name "Net-(ENGINE3-Pad3)") (class "Default")
      (node (ref "ENGINE3") (pin "3") (pinfunction "3_3") (pintype "passive"))
      (node (ref "IC5") (pin "4") (pinfunction "4_4") (pintype "bidirectional"))
      (node (ref "R6") (pin "7") (pinfunction "7_7") (pintype "bidirectional"))
    )
    (net (code "37") (name "Net-(ENGINE4-Pad3)") (class "Default")
      (node (ref "ENGINE4") (pin "3") (pinfunction "3_3") (pintype "passive"))
      (node (ref "IC5") (pin "6") (pinfunction "6_6") (pintype "bidirectional"))
      (node (ref "R6") (pin "8") (pinfunction "8_8") (pintype "bidirectional"))
    )
    (net (code "38") (name "Net-(ENGINE5-Pad3)") (class "Default")
      (node (ref "ENGINE5") (pin "3") (pinfunction "3_3") (pintype "passive"))
      (node (ref "IC3") (pin "4") (pinfunction "4_4") (pintype "bidirectional"))
      (node (ref "R7") (pin "5") (pinfunction "5_5") (pintype "bidirectional"))
    )
    (net (code "39") (name "Net-(ENGINE6-Pad3)") (class "Default")
      (node (ref "ENGINE6") (pin "3") (pinfunction "3_3") (pintype "passive"))
      (node (ref "IC3") (pin "6") (pinfunction "6_6") (pintype "bidirectional"))
      (node (ref "R7") (pin "6") (pinfunction "6_6") (pintype "bidirectional"))
    )
    (net (code "40") (name "Net-(ENGINE7-Pad3)") (class "Default")
      (node (ref "ENGINE7") (pin "3") (pinfunction "3_3") (pintype "passive"))
      (node (ref "IC3") (pin "3") (pinfunction "3_3") (pintype "bidirectional"))
      (node (ref "R7") (pin "7") (pinfunction "7_7") (pintype "bidirectional"))
    )
    (net (code "41") (name "Net-(ENGINE8-Pad3)") (class "Default")
      (node (ref "ENGINE8") (pin "3") (pinfunction "3_3") (pintype "passive"))
      (node (ref "IC3") (pin "1") (pinfunction "1_1") (pintype "bidirectional"))
      (node (ref "R7") (pin "8") (pinfunction "8_8") (pintype "bidirectional"))
    )
    (net (code "42") (name "Net-(FLEX-Pad3)") (class "Default")
      (node (ref "FLEX") (pin "3") (pinfunction "3_3") (pintype "bidirectional"))
      (node (ref "IC8") (pin "1") (pinfunction "1_1") (pintype "bidirectional"))
      (node (ref "R4") (pin "3") (pinfunction "3_3") (pintype "bidirectional"))
    )
    (net (code "43") (name "Net-(FLEX-Pad4)") (class "Default")
      (node (ref "FLEX") (pin "4") (pinfunction "4_4") (pintype "bidirectional"))
      (node (ref "IC8") (pin "6") (pinfunction "6_6") (pintype "bidirectional"))
      (node (ref "R4") (pin "4") (pinfunction "4_4") (pintype "bidirectional"))
    )
    (net (code "44") (name "Net-(IC1A-BOOT0)") (class "Default")
      (node (ref "IC1") (pin "60") (pinfunction "BOOT0_60") (pintype "bidirectional"))
      (node (ref "R11") (pin "2") (pinfunction "2_2") (pintype "passive"))
    )
    (net (code "45") (name "Net-(IC1A-PH0{slash}OSC_IN)") (class "Default")
      (node (ref "C21") (pin "2") (pinfunction "2_2") (pintype "passive"))
      (node (ref "IC1") (pin "5") (pinfunction "PH0/OSC_IN_5") (pintype "bidirectional"))
      (node (ref "Q1") (pin "3") (pinfunction "2_3") (pintype "passive"))
    )
    (net (code "46") (name "Net-(IC1A-PH1{slash}OSC_OUT)") (class "Default")
      (node (ref "C20") (pin "2") (pinfunction "2_2") (pintype "passive"))
      (node (ref "IC1") (pin "6") (pinfunction "PH1/OSC_OUT_6") (pintype "bidirectional"))
      (node (ref "Q1") (pin "1") (pinfunction "1_1") (pintype "passive"))
    )
    (net (code "47") (name "Net-(IC1B-PA9{slash}USART1_TX{slash}TIM1_CH2{slash}I2C3_SMBA{slash}OTG_FS_VBUS)") (class "Default")
      (node (ref "IC1") (pin "42") (pinfunction "PA9/USART1_TX/TIM1_CH2/I2C3_SMBA/OTG_FS_VBUS_42") (pintype "bidirectional"))
      (node (ref "R10") (pin "1") (pinfunction "1_1") (pintype "passive"))
    )
    (net (code "48") (name "Net-(IC1D-PC0{slash}ADC123_IN10)") (class "Default")
      (node (ref "IC1") (pin "8") (pinfunction "PC0/ADC123_IN10_8") (pintype "bidirectional"))
      (node (ref "R1") (pin "4") (pinfunction "4_4") (pintype "bidirectional"))
    )
    (net (code "49") (name "Net-(IC1D-PC1{slash}ADC123_IN11)") (class "Default")
      (node (ref "IC1") (pin "9") (pinfunction "PC1/ADC123_IN11_9") (pintype "bidirectional"))
      (node (ref "R1") (pin "3") (pinfunction "3_3") (pintype "bidirectional"))
    )
    (net (code "50") (name "Net-(IC1E-VCAP1)") (class "Default")
      (node (ref "C22") (pin "1") (pinfunction "1_1") (pintype "passive"))
      (node (ref "IC1") (pin "31") (pinfunction "VCAP1_31") (pintype "bidirectional"))
    )
    (net (code "51") (name "Net-(IC1E-VCAP2)") (class "Default")
      (node (ref "C23") (pin "1") (pinfunction "1_1") (pintype "passive"))
      (node (ref "IC1") (pin "47") (pinfunction "VCAP2_47") (pintype "bidirectional"))
    )
    (net (code "52") (name "Net-(IC4-CPOUT)") (class "Default")
      (node (ref "C24") (pin "1") (pinfunction "1_1") (pintype "passive"))
      (node (ref "IC4") (pin "20") (pinfunction "CPOUT_20") (pintype "bidirectional"))
    )
    (net (code "53") (name "Net-(IC4-REGOUT)") (class "Default")
      (node (ref "C18") (pin "1") (pinfunction "1_1") (pintype "passive"))
      (node (ref "IC4") (pin "10") (pinfunction "REGOUT_10") (pintype "bidirectional"))
    )
    (net (code "54") (name "Net-(IC7-Pad1)") (class "Default")
      (node (ref "IC7") (pin "1") (pinfunction "1_1") (pintype "bidirectional"))
      (node (ref "R3") (pin "5") (pinfunction "5_5") (pintype "bidirectional"))
      (node (ref "RC") (pin "5") (pinfunction "5_5") (pintype "bidirectional"))
    )
    (net (code "55") (name "Net-(IC7-Pad3)") (class "Default")
      (node (ref "IC7") (pin "3") (pinfunction "3_3") (pintype "bidirectional"))
      (node (ref "R3") (pin "6") (pinfunction "6_6") (pintype "bidirectional"))
      (node (ref "RC") (pin "6") (pinfunction "6_6") (pintype "bidirectional"))
    )
    (net (code "56") (name "Net-(IC7-Pad4)") (class "Default")
      (node (ref "IC7") (pin "4") (pinfunction "4_4") (pintype "bidirectional"))
      (node (ref "R3") (pin "7") (pinfunction "7_7") (pintype "bidirectional"))
      (node (ref "RC") (pin "7") (pinfunction "7_7") (pintype "bidirectional"))
    )
    (net (code "57") (name "Net-(IC7-Pad6)") (class "Default")
      (node (ref "IC7") (pin "6") (pinfunction "6_6") (pintype "bidirectional"))
      (node (ref "R3") (pin "8") (pinfunction "8_8") (pintype "bidirectional"))
      (node (ref "RC") (pin "8") (pinfunction "8_8") (pintype "bidirectional"))
    )
    (net (code "58") (name "Net-(IC9-C1)") (class "Default")
      (node (ref "C25") (pin "1") (pinfunction "1_1") (pintype "passive"))
      (node (ref "IC9") (pin "10") (pinfunction "C1_10") (pintype "bidirectional"))
    )
    (net (code "59") (name "Net-(IC9-SETC)") (class "Default")
      (node (ref "C26") (pin "2") (pinfunction "2_2") (pintype "passive"))
      (node (ref "IC9") (pin "12") (pinfunction "SETC_12") (pintype "bidirectional"))
    )
    (net (code "60") (name "Net-(IC9-SETP)") (class "Default")
      (node (ref "C26") (pin "1") (pinfunction "1_1") (pintype "passive"))
      (node (ref "IC9") (pin "8") (pinfunction "SETP_8") (pintype "bidirectional"))
    )
    (net (code "61") (name "Net-(IC11-Pad3)") (class "Default")
      (node (ref "IC11") (pin "3") (pinfunction "3_3") (pintype "bidirectional"))
      (node (ref "R2") (pin "8") (pinfunction "8_8") (pintype "bidirectional"))
      (node (ref "RC") (pin "4") (pinfunction "4_4") (pintype "bidirectional"))
    )
    (net (code "62") (name "Net-(IC11-Pad4)") (class "Default")
      (node (ref "IC11") (pin "4") (pinfunction "4_4") (pintype "bidirectional"))
      (node (ref "R2") (pin "7") (pinfunction "7_7") (pintype "bidirectional"))
      (node (ref "RC") (pin "3") (pinfunction "3_3") (pintype "bidirectional"))
    )
    (net (code "63") (name "Net-(MMCX1-SIGNAL)") (class "Default")
      (node (ref "MMCX1") (pin "S") (pinfunction "SIGNAL_S") (pintype "bidirectional"))
      (node (ref "MODULE1") (pin "1") (pinfunction "ANT_1") (pintype "bidirectional"))
    )
    (net (code "64") (name "Net-(MODULE1-GPIO0)") (class "Default")
      (node (ref "MODULE1") (pin "4") (pinfunction "TXANT_4") (pintype "input"))
      (node (ref "MODULE1") (pin "6") (pinfunction "GPIO0_6") (pintype "bidirectional"))
    )
    (net (code "65") (name "Net-(MODULE1-GPIO1)") (class "Default")
      (node (ref "MODULE1") (pin "3") (pinfunction "RXANT_3") (pintype "input"))
      (node (ref "MODULE1") (pin "7") (pinfunction "GPIO1_7") (pintype "bidirectional"))
    )
    (net (code "66") (name "Net-(PWR-PadA)") (class "Default")
      (node (ref "PWR") (pin "A") (pinfunction "A_A") (pintype "passive"))
      (node (ref "R2") (pin "5") (pinfunction "5_5") (pintype "bidirectional"))
    )
    (net (code "67") (name "Net-(R1-Pad5)") (class "Default")
      (node (ref "R1") (pin "5") (pinfunction "5_5") (pintype "bidirectional"))
      (node (ref "U2") (pin "A") (pinfunction "A_A") (pintype "passive"))
    )
    (net (code "68") (name "Net-(R1-Pad6)") (class "Default")
      (node (ref "R1") (pin "6") (pinfunction "6_6") (pintype "bidirectional"))
      (node (ref "U1") (pin "A") (pinfunction "A_A") (pintype "passive"))
    )
    (net (code "69") (name "Net-(USB1-D+)") (class "Default")
      (node (ref "IC12") (pin "6") (pinfunction "6_6") (pintype "bidirectional"))
      (node (ref "R8") (pin "2") (pinfunction "2_2") (pintype "passive"))
      (node (ref "USB1") (pin "3") (pinfunction "D+_3") (pintype "bidirectional"))
    )
    (net (code "70") (name "Net-(USB1-D-)") (class "Default")
      (node (ref "IC12") (pin "1") (pinfunction "1_1") (pintype "bidirectional"))
      (node (ref "R9") (pin "2") (pinfunction "2_2") (pintype "passive"))
      (node (ref "USB1") (pin "2") (pinfunction "D-_2") (pintype "bidirectional"))
    )
    (net (code "71") (name "RF_IRQ") (class "Default")
      (node (ref "IC1") (pin "4") (pinfunction "PC15/OSC32_OUT_4") (pintype "bidirectional"))
      (node (ref "MODULE1") (pin "14") (pinfunction "NIRQ_14") (pintype "output"))
    )
    (net (code "72") (name "RF_MISO") (class "Default")
      (node (ref "IC1") (pin "22") (pinfunction "PA6/SPI1_MISO/TIM13_CH1/TIM3_CH1/ADC12_IN6_22") (pintype "bidirectional"))
      (node (ref "IC13") (pin "2") (pinfunction "MISO_2") (pintype "bidirectional"))
      (node (ref "MODULE1") (pin "10") (pinfunction "SDO_10") (pintype "output"))
    )
    (net (code "73") (name "RF_MOSI") (class "Default")
      (node (ref "IC1") (pin "23") (pinfunction "PA7/SPI1_MOSI/TIM14_CH1/TIM3_CH2/ADC12_IN7_23") (pintype "bidirectional"))
      (node (ref "IC13") (pin "5") (pinfunction "MOSI_5") (pintype "bidirectional"))
      (node (ref "MODULE1") (pin "11") (pinfunction "SDI_11") (pintype "input"))
    )
    (net (code "74") (name "RF_SCLK") (class "Default")
      (node (ref "IC1") (pin "21") (pinfunction "PA5/SPI1_SCK/ADC12_IN5/DAC2_OUT_21") (pintype "bidirectional"))
      (node (ref "IC13") (pin "6") (pinfunction "SCK_6") (pintype "bidirectional"))
      (node (ref "MODULE1") (pin "12") (pinfunction "SCLK_12") (pintype "input"))
    )
    (net (code "75") (name "RF_SEL") (class "Default")
      (node (ref "IC1") (pin "20") (pinfunction "PA4/SPI1_NSS/SPI3_NSS/ADC12_IN4/DAC1_OUT_20") (pintype "bidirectional"))
      (node (ref "MODULE1") (pin "13") (pinfunction "NSEL_13") (pintype "input"))
    )
    (net (code "76") (name "RXD3") (class "Default")
      (node (ref "IC1") (pin "52") (pinfunction "PC11/SPI3_MISO/UART4_RX/USART3_RX_52") (pintype "bidirectional"))
      (node (ref "R5") (pin "5") (pinfunction "5_5") (pintype "bidirectional"))
    )
    (net (code "77") (name "RXD4") (class "Default")
      (node (ref "IC1") (pin "15") (pinfunction "PA1/USART4_RX/TIM5_CH2/TIM2_CH2/ADC123_IN1_15") (pintype "bidirectional"))
      (node (ref "R4") (pin "8") (pinfunction "8_8") (pintype "bidirectional"))
    )
    (net (code "78") (name "RXD5") (class "Default")
      (node (ref "IC1") (pin "54") (pinfunction "PD2/UART5_RX_54") (pintype "bidirectional"))
      (node (ref "R5") (pin "8") (pinfunction "8_8") (pintype "bidirectional"))
    )
    (net (code "79") (name "SCL") (class "Default")
      (node (ref "IC1") (pin "29") (pinfunction "PB10/SPI2_SCK/I2C2_SCL/USART3_TX/TIM2_CH3_29") (pintype "bidirectional"))
      (node (ref "IC2") (pin "8") (pinfunction "SCLK_8") (pintype "bidirectional"))
      (node (ref "IC4") (pin "23") (pinfunction "SCL_23") (pintype "bidirectional"))
      (node (ref "IC9") (pin "1") (pinfunction "SCL_1") (pintype "bidirectional"))
      (node (ref "R13") (pin "2") (pinfunction "2_2") (pintype "passive"))
    )
    (net (code "80") (name "SDA") (class "Default")
      (node (ref "IC1") (pin "30") (pinfunction "PB11/I2C2_SDA/USART3_RX/TIM2_CH4_30") (pintype "bidirectional"))
      (node (ref "IC2") (pin "7") (pinfunction "SDA/SDI_7") (pintype "bidirectional"))
      (node (ref "IC4") (pin "24") (pinfunction "SDA_24") (pintype "bidirectional"))
      (node (ref "IC9") (pin "16") (pinfunction "SDA_16") (pintype "bidirectional"))
      (node (ref "R14") (pin "2") (pinfunction "2_2") (pintype "passive"))
    )
    (net (code "81") (name "SWCLK") (class "Default")
      (node (ref "IC1") (pin "49") (pinfunction "PA14/JTCK-SWCLK_49") (pintype "bidirectional"))
      (node (ref "SWD") (pin "1") (pinfunction "1_1") (pintype "bidirectional"))
    )
    (net (code "82") (name "SWDIO") (class "Default")
      (node (ref "IC1") (pin "46") (pinfunction "PA13/JTMS-SWDIO_46") (pintype "bidirectional"))
      (node (ref "SWD") (pin "2") (pinfunction "2_2") (pintype "bidirectional"))
    )
    (net (code "83") (name "TXD3") (class "Default")
      (node (ref "IC1") (pin "51") (pinfunction "PC10/SPI3_SCK/UART4_TX/USART3_TX_51") (pintype "bidirectional"))
      (node (ref "R5") (pin "6") (pinfunction "6_6") (pintype "bidirectional"))
    )
    (net (code "84") (name "TXD4") (class "Default")
      (node (ref "IC1") (pin "14") (pinfunction "PA0/USART4_TX/TIM5_CH1/ADC123_IN0/WKUP_14") (pintype "bidirectional"))
      (node (ref "R4") (pin "7") (pinfunction "7_7") (pintype "bidirectional"))
    )
    (net (code "85") (name "TXD5") (class "Default")
      (node (ref "IC1") (pin "53") (pinfunction "PC12/UART5_TX/SPI3_MOSI_53") (pintype "bidirectional"))
      (node (ref "R5") (pin "7") (pinfunction "7_7") (pintype "bidirectional"))
    )
    (net (code "86") (name "VCC") (class "Default")
      (node (ref "IC12") (pin "2") (pinfunction "2_2") (pintype "bidirectional"))
      (node (ref "L2") (pin "1") (pinfunction "1_1") (pintype "passive"))
      (node (ref "R10") (pin "2") (pinfunction "2_2") (pintype "passive"))
      (node (ref "USB1") (pin "1") (pinfunction "VBUS_1") (pintype "bidirectional"))
    )
    (net (code "87") (name "VCCA") (class "Default")
      (node (ref "C13") (pin "1") (pinfunction "1_1") (pintype "passive"))
      (node (ref "C14") (pin "1") (pinfunction "1_1") (pintype "passive"))
      (node (ref "C15") (pin "1") (pinfunction "1_1") (pintype "passive"))
      (node (ref "C16") (pin "1") (pinfunction "1_1") (pintype "passive"))
      (node (ref "C2") (pin "1") (pinfunction "1_1") (pintype "passive"))
      (node (ref "IC2") (pin "1") (pinfunction "VCC_1") (pintype "bidirectional"))
      (node (ref "IC2") (pin "2") (pinfunction "PS_2") (pintype "bidirectional"))
      (node (ref "IC4") (pin "13") (pinfunction "VDD_13") (pintype "bidirectional"))
      (node (ref "IC4") (pin "8") (pinfunction "VLOGIC_8") (pintype "bidirectional"))
      (node (ref "IC4") (pin "9") (pinfunction "AD0_9") (pintype "bidirectional"))
      (node (ref "IC9") (pin "13") (pinfunction "VDDIO_13") (pintype "bidirectional"))
      (node (ref "IC9") (pin "2") (pinfunction "VDD_2") (pintype "bidirectional"))
      (node (ref "IC9") (pin "4") (pinfunction "S1_4") (pintype "bidirectional"))
      (node (ref "L1") (pin "2") (pinfunction "2_2") (pintype "passive"))
    )
    (net (code "88") (name "unconnected-(IC1B-PA8{slash}TIM1_CH1{slash}I2C3_SCL-Pad41)") (class "Default")
      (node (ref "IC1") (pin "41") (pinfunction "PA8/TIM1_CH1/I2C3_SCL_41") (pintype "bidirectional"))
    )
    (net (code "89") (name "unconnected-(IC1B-PA10{slash}USART1_RX{slash}TIM1_CH3{slash}OTG_FS_ID-Pad43)") (class "Default")
      (node (ref "IC1") (pin "43") (pinfunction "PA10/USART1_RX/TIM1_CH3/OTG_FS_ID_43") (pintype "bidirectional"))
    )
    (net (code "90") (name "unconnected-(IC1B-PA15{slash}JTDI{slash}SPI3_NSS{slash}I2S3_WS{slash}SPI1_NSS-Pad50)") (class "Default")
      (node (ref "IC1") (pin "50") (pinfunction "PA15/JTDI/SPI3_NSS/I2S3_WS/SPI1_NSS_50") (pintype "bidirectional"))
    )
    (net (code "91") (name "unconnected-(IC1C-PB2{slash}BOOT1-Pad28)") (class "Default")
      (node (ref "IC1") (pin "28") (pinfunction "PB2/BOOT1_28") (pintype "bidirectional"))
    )
    (net (code "92") (name "unconnected-(IC1C-PB3{slash}JTDO{slash}SPI3_SCK{slash}TIM2_CH2{slash}SPI1_SCK-Pad55)") (class "Default")
      (node (ref "IC1") (pin "55") (pinfunction "PB3/JTDO/SPI3_SCK/TIM2_CH2/SPI1_SCK_55") (pintype "bidirectional"))
    )
    (net (code "93") (name "unconnected-(IC1C-PB4{slash}~{NJTRST}{slash}SPI3_MISO{slash}TIM3_CH1{slash}SPI1_MISO-Pad56)") (class "Default")
      (node (ref "IC1") (pin "56") (pinfunction "PB4/~{NJTRST}/SPI3_MISO/TIM3_CH1/SPI1_MISO_56") (pintype "bidirectional"))
    )
    (net (code "94") (name "unconnected-(IC1C-PB5{slash}I2C1_SMBA{slash}CAN2_RX{slash}TIM3_CH2{slash}SPI1_MOSI{slash}SPI3_MOSI-Pad57)") (class "Default")
      (node (ref "IC1") (pin "57") (pinfunction "PB5/I2C1_SMBA/CAN2_RX/TIM3_CH2/SPI1_MOSI/SPI3_MOSI_57") (pintype "bidirectional"))
    )
    (net (code "95") (name "unconnected-(IC1D-PC2{slash}SPI2_MISO{slash}ADC123_IN12-Pad10)") (class "Default")
      (node (ref "IC1") (pin "10") (pinfunction "PC2/SPI2_MISO/ADC123_IN12_10") (pintype "bidirectional"))
    )
    (net (code "96") (name "unconnected-(IC1D-PC3{slash}SPI2_MOSI{slash}ADC123_IN13-Pad11)") (class "Default")
      (node (ref "IC1") (pin "11") (pinfunction "PC3/SPI2_MOSI/ADC123_IN13_11") (pintype "bidirectional"))
    )
    (net (code "97") (name "unconnected-(IC1D-PC5{slash}ADC12_IN15-Pad25)") (class "Default")
      (node (ref "IC1") (pin "25") (pinfunction "PC5/ADC12_IN15_25") (pintype "bidirectional"))
    )
    (net (code "98") (name "unconnected-(IC2-SDO-Pad6)") (class "Default")
      (node (ref "IC2") (pin "6") (pinfunction "SDO_6") (pintype "bidirectional"))
    )
    (net (code "99") (name "unconnected-(IC3-Pad2)") (class "Default")
      (node (ref "IC3") (pin "2") (pinfunction "2_2") (pintype "bidirectional"))
    )
    (net (code "100") (name "unconnected-(IC4-AUX_CLK-Pad7)") (class "Default")
      (node (ref "IC4") (pin "7") (pinfunction "AUX_CLK_7") (pintype "bidirectional"))
    )
    (net (code "101") (name "unconnected-(IC4-AUX_DA-Pad6)") (class "Default")
      (node (ref "IC4") (pin "6") (pinfunction "AUX_DA_6") (pintype "bidirectional"))
    )
    (net (code "102") (name "unconnected-(IC4-CLKIN-Pad1)") (class "Default")
      (node (ref "IC4") (pin "1") (pinfunction "CLKIN_1") (pintype "bidirectional"))
    )
    (net (code "103") (name "unconnected-(IC4-CLKOUT-Pad22)") (class "Default")
      (node (ref "IC4") (pin "22") (pinfunction "CLKOUT_22") (pintype "bidirectional"))
    )
    (net (code "104") (name "unconnected-(IC4-FSYNC-Pad11)") (class "Default")
      (node (ref "IC4") (pin "11") (pinfunction "FSYNC_11") (pintype "bidirectional"))
    )
    (net (code "105") (name "unconnected-(IC4-RESV-Pad19)") (class "Default")
      (node (ref "IC4") (pin "19") (pinfunction "RESV_19") (pintype "bidirectional"))
    )
    (net (code "106") (name "unconnected-(IC4-RESV-Pad21)") (class "Default")
      (node (ref "IC4") (pin "21") (pinfunction "RESV_21") (pintype "bidirectional"))
    )
    (net (code "107") (name "unconnected-(IC5-Pad2)") (class "Default")
      (node (ref "IC5") (pin "2") (pinfunction "2_2") (pintype "bidirectional"))
    )
    (net (code "108") (name "unconnected-(IC6-BP-Pad4)") (class "Default")
      (node (ref "IC6") (pin "4") (pinfunction "BP_4") (pintype "input"))
    )
    (net (code "109") (name "unconnected-(IC7-Pad2)") (class "Default")
      (node (ref "IC7") (pin "2") (pinfunction "2_2") (pintype "bidirectional"))
    )
    (net (code "110") (name "unconnected-(IC8-Pad2)") (class "Default")
      (node (ref "IC8") (pin "2") (pinfunction "2_2") (pintype "bidirectional"))
    )
    (net (code "111") (name "unconnected-(IC9-NC-Pad3)") (class "Default")
      (node (ref "IC9") (pin "3") (pinfunction "NC_3") (pintype "bidirectional"))
    )
    (net (code "112") (name "unconnected-(IC9-NC-Pad5)") (class "Default")
      (node (ref "IC9") (pin "5") (pinfunction "NC_5") (pintype "bidirectional"))
    )
    (net (code "113") (name "unconnected-(IC9-NC-Pad6)") (class "Default")
      (node (ref "IC9") (pin "6") (pinfunction "NC_6") (pintype "bidirectional"))
    )
    (net (code "114") (name "unconnected-(IC9-NC-Pad7)") (class "Default")
      (node (ref "IC9") (pin "7") (pinfunction "NC_7") (pintype "bidirectional"))
    )
    (net (code "115") (name "unconnected-(IC9-NC-Pad14)") (class "Default")
      (node (ref "IC9") (pin "14") (pinfunction "NC_14") (pintype "bidirectional"))
    )
    (net (code "116") (name "unconnected-(IC10-Pad2)") (class "Default")
      (node (ref "IC10") (pin "2") (pinfunction "2_2") (pintype "bidirectional"))
    )
    (net (code "117") (name "unconnected-(IC11-Pad1)") (class "Default")
      (node (ref "IC11") (pin "1") (pinfunction "1_1") (pintype "bidirectional"))
    )
    (net (code "118") (name "unconnected-(IC11-Pad2)") (class "Default")
      (node (ref "IC11") (pin "2") (pinfunction "2_2") (pintype "bidirectional"))
    )
    (net (code "119") (name "unconnected-(IC11-Pad6)") (class "Default")
      (node (ref "IC11") (pin "6") (pinfunction "6_6") (pintype "bidirectional"))
    )
    (net (code "120") (name "unconnected-(IC12-Pad3)") (class "Default")
      (node (ref "IC12") (pin "3") (pinfunction "3_3") (pintype "bidirectional"))
    )
    (net (code "121") (name "unconnected-(IC12-Pad4)") (class "Default")
      (node (ref "IC12") (pin "4") (pinfunction "4_4") (pintype "bidirectional"))
    )
    (net (code "122") (name "unconnected-(MODULE1-GPIO2-Pad8)") (class "Default")
      (node (ref "MODULE1") (pin "8") (pinfunction "GPIO2_8") (pintype "bidirectional"))
    )
    (net (code "123") (name "unconnected-(R1-Pad1)") (class "Default")
      (node (ref "R1") (pin "1") (pinfunction "1_1") (pintype "bidirectional"))
    )
    (net (code "124") (name "unconnected-(R1-Pad2)") (class "Default")
      (node (ref "R1") (pin "2") (pinfunction "2_2") (pintype "bidirectional"))
    )
    (net (code "125") (name "unconnected-(R1-Pad7)") (class "Default")
      (node (ref "R1") (pin "7") (pinfunction "7_7") (pintype "bidirectional"))
    )
    (net (code "126") (name "unconnected-(R1-Pad8)") (class "Default")
      (node (ref "R1") (pin "8") (pinfunction "8_8") (pintype "bidirectional"))
    )
    (net (code "127") (name "unconnected-(R2-Pad3)") (class "Default")
      (node (ref "R2") (pin "3") (pinfunction "3_3") (pintype "bidirectional"))
    )
    (net (code "128") (name "unconnected-(R2-Pad6)") (class "Default")
      (node (ref "R2") (pin "6") (pinfunction "6_6") (pintype "bidirectional"))
    )
    (net (code "129") (name "unconnected-(USB1-ID-Pad4)") (class "Default")
      (node (ref "USB1") (pin "4") (pinfunction "ID_4") (pintype "bidirectional"))
    )
    (net (code "130") (name "~{SRST}") (class "Default")
      (node (ref "C19") (pin "1") (pinfunction "1_1") (pintype "passive"))
      (node (ref "IC1") (pin "7") (pinfunction "~{NRST}_7") (pintype "bidirectional"))
      (node (ref "R12") (pin "2") (pinfunction "2_2") (pintype "passive"))
      (node (ref "SWD") (pin "3") (pinfunction "3_3") (pintype "bidirectional"))
    )
  )
)
